# TheStaticTurtle_oshw-sdi3g-fiber__schema.net
KiCad netlist of a schematic drawn in Altium Designer
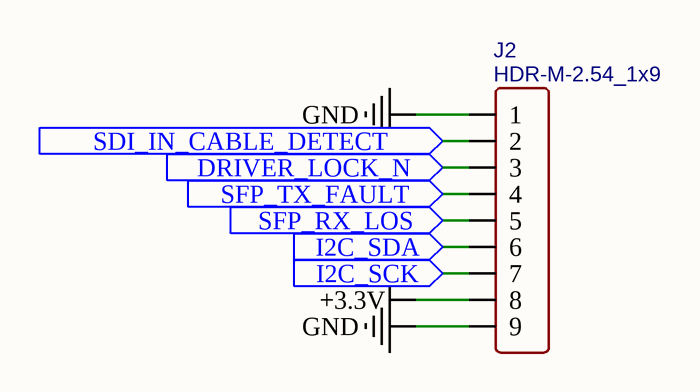
[diagram p0: TheStaticTurtle_oshw-sdi3g-fiber__schematic_V4-Reclocked_OSHW_BiDi_SDI_Fiber_Converter_V4_Reclocker_2024-11-17__Diag.schdoc]

(export (version "E")
  (design (tool "Eeschema 10.0.6"))
  (components
    (comp (ref "J2")
      (value "HDR-M-2.54_1x9")
      (fields (field (name "CONTRIBUTOR") "LCEDA_Lib"))
      (libsource (lib "altium-import") (part "root_0_HDR-M-2.54_1x9_"))
    )
  )
  (nets
    (net (code "1") (name "+3.3V") (class "Default")
      (node (ref "J2") (pin "8") (pinfunction "8_8") (pintype "passive"))
    )
    (net (code "2") (name "/DRIVER_LOCK_N") (class "Default")
      (node (ref "J2") (pin "3") (pinfunction "3_3") (pintype "passive"))
    )
    (net (code "3") (name "/I2C_SCK") (class "Default")
      (node (ref "J2") (pin "7") (pinfunction "7_7") (pintype "passive"))
    )
    (net (code "4") (name "/I2C_SDA") (class "Default")
      (node (ref "J2") (pin "6") (pinfunction "6_6") (pintype "passive"))
    )
    (net (code "5") (name "/SDI_IN_CABLE_DETECT") (class "Default")
      (node (ref "J2") (pin "2") (pinfunction "2_2") (pintype "passive"))
    )
    (net (code "6") (name "/SFP_RX_LOS") (class "Default")
      (node (ref "J2") (pin "5") (pinfunction "5_5") (pintype "passive"))
    )
    (net (code "7") (name "/SFP_TX_FAULT") (class "Default")
      (node (ref "J2") (pin "4") (pinfunction "4_4") (pintype "passive"))
    )
    (net (code "8") (name "GND") (class "Default")
      (node (ref "J2") (pin "1") (pinfunction "1_1") (pintype "passive"))
      (node (ref "J2") (pin "9") (pinfunction "9_9") (pintype "passive"))
    )
  )
)
